# Version_1.net
KiCad netlist of a schematic drawn in EAGLE
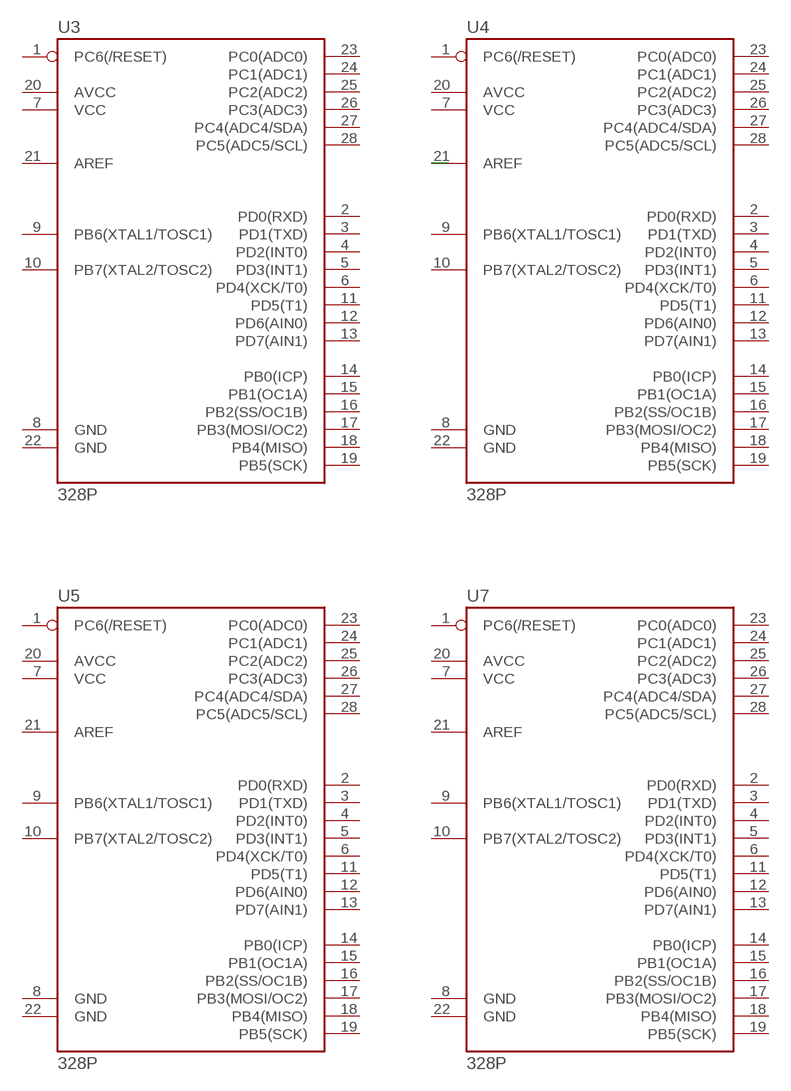
[diagram p0: schematic, sheet 1, part 1 of 2]
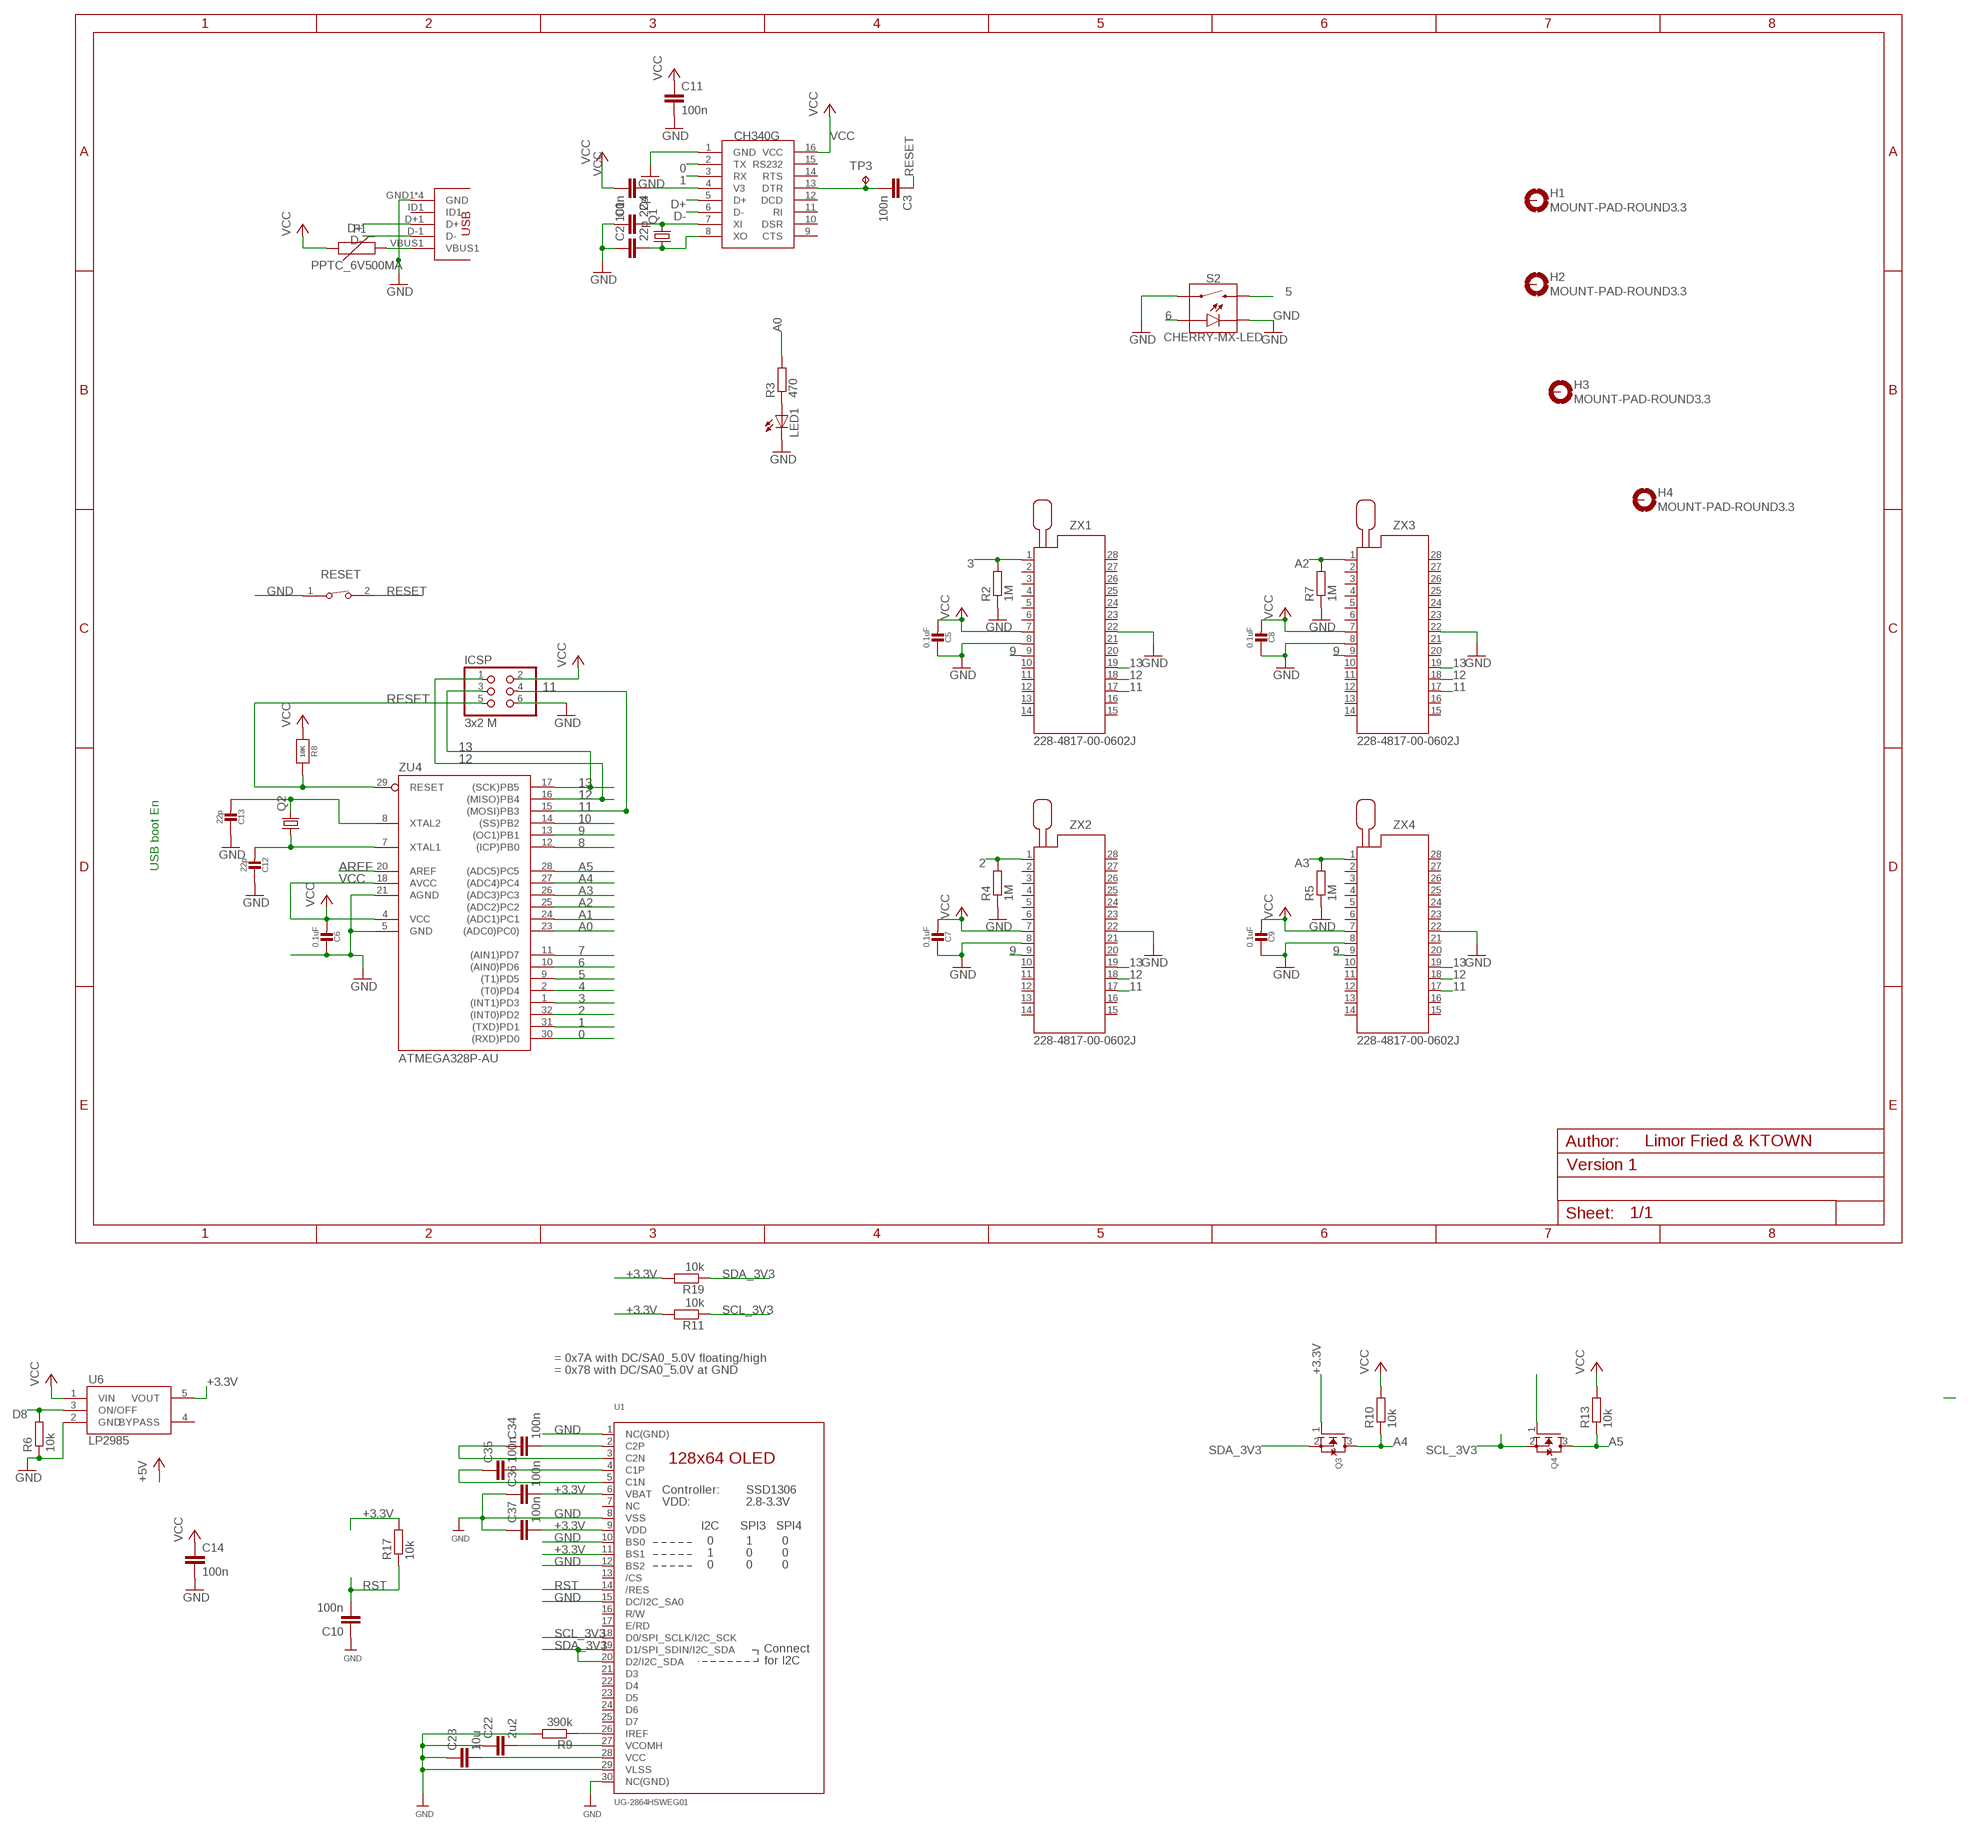
[diagram p1: schematic, sheet 1, part 2 of 2]

(export (version "E")
  (design (tool "Eeschema 10.0.6"))
  (components
    (comp (ref "C1")
      (value "22p")
      (footprint "eagle-import:C0805")
      (libsource (lib "eagle-import") (part "resistor_C-EUC0805"))
    )
    (comp (ref "C2")
      (value "22p")
      (footprint "eagle-import:C0805")
      (libsource (lib "eagle-import") (part "resistor_C-EUC0805"))
    )
    (comp (ref "C3")
      (value "100n")
      (footprint "eagle-import:C0805")
      (libsource (lib "eagle-import") (part "resistor_C-EUC0805"))
    )
    (comp (ref "C4")
      (value "100n")
      (footprint "eagle-import:C0805")
      (libsource (lib "eagle-import") (part "resistor_C-EUC0805"))
    )
    (comp (ref "C5")
      (value "0.1uF")
      (footprint "eagle-import:0805-NO")
      (libsource (lib "eagle-import") (part "CAP_CERAMIC0805-NOOUTLINE"))
    )
    (comp (ref "C6")
      (value "0.1uF")
      (footprint "eagle-import:0805-NO")
      (libsource (lib "eagle-import") (part "CAP_CERAMIC0805-NOOUTLINE"))
    )
    (comp (ref "C7")
      (value "0.1uF")
      (footprint "eagle-import:0805-NO")
      (libsource (lib "eagle-import") (part "CAP_CERAMIC0805-NOOUTLINE"))
    )
    (comp (ref "C8")
      (value "0.1uF")
      (footprint "eagle-import:0805-NO")
      (libsource (lib "eagle-import") (part "CAP_CERAMIC0805-NOOUTLINE"))
    )
    (comp (ref "C9")
      (value "0.1uF")
      (footprint "eagle-import:0805-NO")
      (libsource (lib "eagle-import") (part "CAP_CERAMIC0805-NOOUTLINE"))
    )
    (comp (ref "C10")
      (value "100n")
      (footprint "eagle-import:C0805")
      (libsource (lib "eagle-import") (part "C-EUC0805"))
    )
    (comp (ref "C11")
      (value "100n")
      (footprint "eagle-import:C0805")
      (libsource (lib "eagle-import") (part "resistor_C-EUC0805"))
    )
    (comp (ref "C12")
      (value "22p")
      (footprint "eagle-import:0805_10MGAP")
      (libsource (lib "eagle-import") (part "CAP_CERAMIC0805_10MGAP"))
    )
    (comp (ref "C13")
      (value "22p")
      (footprint "eagle-import:0805_10MGAP")
      (libsource (lib "eagle-import") (part "CAP_CERAMIC0805_10MGAP"))
    )
    (comp (ref "C14")
      (value "100n")
      (footprint "eagle-import:C0805")
      (libsource (lib "eagle-import") (part "resistor_C-EUC0805"))
    )
    (comp (ref "C22")
      (value "2u2")
      (footprint "eagle-import:C0805")
      (libsource (lib "eagle-import") (part "C-EUC0805"))
    )
    (comp (ref "C23")
      (value "10u")
      (footprint "eagle-import:C0805")
      (libsource (lib "eagle-import") (part "C-EUC0805"))
    )
    (comp (ref "C34")
      (value "100n")
      (footprint "eagle-import:C0805")
      (libsource (lib "eagle-import") (part "C-EUC0805"))
    )
    (comp (ref "C35")
      (value "100n")
      (footprint "eagle-import:C0805")
      (libsource (lib "eagle-import") (part "C-EUC0805"))
    )
    (comp (ref "C36")
      (value "100n")
      (footprint "eagle-import:C0805")
      (libsource (lib "eagle-import") (part "C-EUC0805"))
    )
    (comp (ref "C37")
      (value "100n")
      (footprint "eagle-import:C0805")
      (libsource (lib "eagle-import") (part "C-EUC0805"))
    )
    (comp (ref "F1")
      (value "PPTC_6V500MA")
      (footprint "eagle-import:0805")
      (libsource (lib "eagle-import") (part "PPTC_6V500MA"))
    )
    (comp (ref "H1")
      (value "MOUNT-PAD-ROUND3.3")
      (footprint "eagle-import:3,3-PAD")
      (libsource (lib "eagle-import") (part "MOUNT-PAD-ROUND3.3"))
    )
    (comp (ref "H2")
      (value "MOUNT-PAD-ROUND3.3")
      (footprint "eagle-import:3,3-PAD")
      (libsource (lib "eagle-import") (part "MOUNT-PAD-ROUND3.3"))
    )
    (comp (ref "H3")
      (value "MOUNT-PAD-ROUND3.3")
      (footprint "eagle-import:3,3-PAD")
      (libsource (lib "eagle-import") (part "MOUNT-PAD-ROUND3.3"))
    )
    (comp (ref "H4")
      (value "MOUNT-PAD-ROUND3.3")
      (footprint "eagle-import:3,3-PAD")
      (libsource (lib "eagle-import") (part "MOUNT-PAD-ROUND3.3"))
    )
    (comp (ref "ICSP")
      (value "3x2 M")
      (footprint "eagle-import:2X03_ROUND_70MIL")
      (libsource (lib "eagle-import") (part "HEADER-2X3"))
    )
    (comp (ref "J1")
      (value "USB-AB")
      (footprint "eagle-import:USB-AB-MICRO-SMD_V02_BOSS")
      (libsource (lib "eagle-import") (part "USB-AB"))
    )
    (comp (ref "LED1")
      (value "LEDCHIPLED_0805")
      (footprint "eagle-import:CHIPLED_0805")
      (libsource (lib "eagle-import") (part "LEDCHIPLED_0805"))
    )
    (comp (ref "Q1")
      (value "CRYSTALHC49S")
      (footprint "eagle-import:HC49_S")
      (libsource (lib "eagle-import") (part "CRYSTALHC49S"))
    )
    (comp (ref "Q2")
      (value "CRYSTALHC49S")
      (footprint "eagle-import:HC49_S")
      (libsource (lib "eagle-import") (part "CRYSTALHC49S"))
    )
    (comp (ref "Q3")
      (value "MOSFET-NREFLOW")
      (footprint "eagle-import:SOT23")
      (libsource (lib "eagle-import") (part "MOSFET-NREFLOW"))
    )
    (comp (ref "Q4")
      (value "MOSFET-NREFLOW")
      (footprint "eagle-import:SOT23")
      (libsource (lib "eagle-import") (part "MOSFET-NREFLOW"))
    )
    (comp (ref "R2")
      (value "1M")
      (footprint "eagle-import:R0805")
      (libsource (lib "eagle-import") (part "resistor_R-EU_R0805"))
    )
    (comp (ref "R3")
      (value "470")
      (footprint "eagle-import:R0805")
      (libsource (lib "eagle-import") (part "resistor_R-EU_R0805"))
    )
    (comp (ref "R4")
      (value "1M")
      (footprint "eagle-import:R0805")
      (libsource (lib "eagle-import") (part "resistor_R-EU_R0805"))
    )
    (comp (ref "R5")
      (value "1M")
      (footprint "eagle-import:R0805")
      (libsource (lib "eagle-import") (part "resistor_R-EU_R0805"))
    )
    (comp (ref "R6")
      (value "10k")
      (footprint "eagle-import:R0805")
      (libsource (lib "eagle-import") (part "R-EU_R0805"))
    )
    (comp (ref "R7")
      (value "1M")
      (footprint "eagle-import:R0805")
      (libsource (lib "eagle-import") (part "resistor_R-EU_R0805"))
    )
    (comp (ref "R8")
      (value "10K")
      (footprint "eagle-import:_0805MP")
      (libsource (lib "eagle-import") (part "RESISTOR_0805MP"))
    )
    (comp (ref "R9")
      (value "390k")
      (footprint "eagle-import:R0805")
      (libsource (lib "eagle-import") (part "R-EU_R0805"))
    )
    (comp (ref "R10")
      (value "10k")
      (footprint "eagle-import:R0805")
      (libsource (lib "eagle-import") (part "R-EU_R0805"))
    )
    (comp (ref "R11")
      (value "10k")
      (footprint "eagle-import:R0805")
      (libsource (lib "eagle-import") (part "R-EU_R0805"))
    )
    (comp (ref "R13")
      (value "10k")
      (footprint "eagle-import:R0805")
      (libsource (lib "eagle-import") (part "R-EU_R0805"))
    )
    (comp (ref "R17")
      (value "10k")
      (footprint "eagle-import:R0805")
      (libsource (lib "eagle-import") (part "R-EU_R0805"))
    )
    (comp (ref "R19")
      (value "10k")
      (footprint "eagle-import:R0805")
      (libsource (lib "eagle-import") (part "R-EU_R0805"))
    )
    (comp (ref "RESET")
      (value "434111043826")
      (footprint "eagle-import:434111043826")
      (libsource (lib "eagle-import") (part "434111043826"))
    )
    (comp (ref "S2")
      (value "CHERRY-MX-LED")
      (footprint "eagle-import:CHERRY-MX-LED")
      (libsource (lib "eagle-import") (part "CHERRY-MX-LED"))
    )
    (comp (ref "TP3")
      (value "TPTP18R")
      (footprint "eagle-import:TP18R")
      (libsource (lib "eagle-import") (part "TPTP18R"))
    )
    (comp (ref "U1")
      (value "UG-2864HSWEG01")
      (footprint "eagle-import:UG-2864HSWEG01_0.96IN_WRAPAROUND")
      (libsource (lib "eagle-import") (part "DISP_OLED_UG-2864HSWEG010.96{dblquote}"))
    )
    (comp (ref "U2")
      (value "CH340G")
      (footprint "eagle-import:SOIC16")
      (libsource (lib "eagle-import") (part "CH340G"))
    )
    (comp (ref "U3")
      (value "328P")
      (footprint "eagle-import:DIP28")
      (libsource (lib "eagle-import") (part "ATMEGA328P_PDIP"))
    )
    (comp (ref "U4")
      (value "328P")
      (footprint "eagle-import:DIP28")
      (libsource (lib "eagle-import") (part "ATMEGA328P_PDIP"))
    )
    (comp (ref "U5")
      (value "328P")
      (footprint "eagle-import:DIP28")
      (libsource (lib "eagle-import") (part "ATMEGA328P_PDIP"))
    )
    (comp (ref "U6")
      (value "LP2985AIM5-3.3")
      (footprint "eagle-import:SOT25")
      (libsource (lib "eagle-import") (part "LP2985AIM5-3.3"))
    )
    (comp (ref "U7")
      (value "328P")
      (footprint "eagle-import:DIP28")
      (libsource (lib "eagle-import") (part "ATMEGA328P_PDIP"))
    )
    (comp (ref "ZU4")
      (value "ATMEGA328P-AU")
      (footprint "eagle-import:TQFP32-08")
      (libsource (lib "eagle-import") (part "ATMEGA328P-AU"))
    )
    (comp (ref "ZX1")
      (value "228-4817-00-0602J")
      (footprint "eagle-import:228-4817-00-0602J")
      (fields (field (name "MF") "3M"))
      (libsource (lib "eagle-import") (part "228-?00-0602J4817-"))
    )
    (comp (ref "ZX2")
      (value "228-4817-00-0602J")
      (footprint "eagle-import:228-4817-00-0602J")
      (fields (field (name "MF") "3M"))
      (libsource (lib "eagle-import") (part "228-?00-0602J4817-"))
    )
    (comp (ref "ZX3")
      (value "228-4817-00-0602J")
      (footprint "eagle-import:228-4817-00-0602J")
      (fields (field (name "MF") "3M"))
      (libsource (lib "eagle-import") (part "228-?00-0602J4817-"))
    )
    (comp (ref "ZX4")
      (value "228-4817-00-0602J")
      (footprint "eagle-import:228-4817-00-0602J")
      (fields (field (name "MF") "3M"))
      (libsource (lib "eagle-import") (part "228-?00-0602J4817-"))
    )
  )
  (nets
    (net (code "2") (name "/+3.3V") (class "Default")
      (node (ref "C36") (pin "2") (pinfunction "2_2") (pintype "passive"))
      (node (ref "C37") (pin "2") (pinfunction "2_2") (pintype "passive"))
      (node (ref "Q3") (pin "1") (pinfunction "G_1") (pintype "bidirectional"))
      (node (ref "Q4") (pin "1") (pinfunction "G_1") (pintype "bidirectional"))
      (node (ref "R11") (pin "2") (pinfunction "2_2") (pintype "passive"))
      (node (ref "R17") (pin "2") (pinfunction "2_2") (pintype "passive"))
      (node (ref "R19") (pin "2") (pinfunction "2_2") (pintype "passive"))
      (node (ref "U1") (pin "11") (pinfunction "BS1_11") (pintype "input"))
      (node (ref "U1") (pin "6") (pinfunction "VBAT_6") (pintype "input"))
      (node (ref "U1") (pin "9") (pinfunction "VDD_9") (pintype "power_in"))
      (node (ref "U6") (pin "5") (pinfunction "VOUT_5") (pintype "power_in"))
    )
    (net (code "3") (name "/0") (class "Default")
      (node (ref "U2") (pin "2") (pinfunction "TX_2") (pintype "bidirectional"))
      (node (ref "ZU4") (pin "30") (pinfunction "(RXD)PD0_30") (pintype "bidirectional"))
    )
    (net (code "4") (name "/1") (class "Default")
      (node (ref "U2") (pin "3") (pinfunction "RX_3") (pintype "bidirectional"))
      (node (ref "ZU4") (pin "31") (pinfunction "(TXD)PD1_31") (pintype "bidirectional"))
    )
    (net (code "5") (name "/2") (class "Default")
      (node (ref "R4") (pin "2") (pinfunction "2_2") (pintype "passive"))
      (node (ref "ZU4") (pin "32") (pinfunction "(INT0)PD2_32") (pintype "bidirectional"))
      (node (ref "ZX2") (pin "1") (pinfunction "1_1") (pintype "passive"))
    )
    (net (code "6") (name "/3") (class "Default")
      (node (ref "R2") (pin "2") (pinfunction "2_2") (pintype "passive"))
      (node (ref "ZU4") (pin "1") (pinfunction "(INT1)PD3_1") (pintype "bidirectional"))
      (node (ref "ZX1") (pin "1") (pinfunction "1_1") (pintype "passive"))
    )
    (net (code "7") (name "/4") (class "Default")
      (node (ref "ZU4") (pin "2") (pinfunction "(T0)PD4_2") (pintype "bidirectional"))
    )
    (net (code "8") (name "/5") (class "Default")
      (node (ref "S2") (pin "S2") (pinfunction "S2_S2") (pintype "passive"))
      (node (ref "ZU4") (pin "9") (pinfunction "(T1)PD5_9") (pintype "bidirectional"))
    )
    (net (code "9") (name "/6") (class "Default")
      (node (ref "S2") (pin "A") (pinfunction "A_A") (pintype "passive"))
      (node (ref "ZU4") (pin "10") (pinfunction "(AIN0)PD6_10") (pintype "bidirectional"))
    )
    (net (code "10") (name "/7") (class "Default")
      (node (ref "ZU4") (pin "11") (pinfunction "(AIN1)PD7_11") (pintype "bidirectional"))
    )
    (net (code "11") (name "/8") (class "Default")
      (node (ref "ZU4") (pin "12") (pinfunction "(ICP)PB0_12") (pintype "bidirectional"))
    )
    (net (code "12") (name "/9") (class "Default")
      (node (ref "ZU4") (pin "13") (pinfunction "(OC1)PB1_13") (pintype "bidirectional"))
      (node (ref "ZX1") (pin "9") (pinfunction "9_9") (pintype "passive"))
      (node (ref "ZX2") (pin "9") (pinfunction "9_9") (pintype "passive"))
      (node (ref "ZX3") (pin "9") (pinfunction "9_9") (pintype "passive"))
      (node (ref "ZX4") (pin "9") (pinfunction "9_9") (pintype "passive"))
    )
    (net (code "13") (name "/10") (class "Default")
      (node (ref "ZU4") (pin "14") (pinfunction "(SS)PB2_14") (pintype "bidirectional"))
    )
    (net (code "14") (name "/11") (class "Default")
      (node (ref "ICSP") (pin "4") (pinfunction "4_4") (pintype "passive"))
      (node (ref "ZU4") (pin "15") (pinfunction "(MOSI)PB3_15") (pintype "bidirectional"))
      (node (ref "ZX1") (pin "17") (pinfunction "17_17") (pintype "passive"))
      (node (ref "ZX2") (pin "17") (pinfunction "17_17") (pintype "passive"))
      (node (ref "ZX3") (pin "17") (pinfunction "17_17") (pintype "passive"))
      (node (ref "ZX4") (pin "17") (pinfunction "17_17") (pintype "passive"))
    )
    (net (code "15") (name "/12") (class "Default")
      (node (ref "ICSP") (pin "1") (pinfunction "1_1") (pintype "passive"))
      (node (ref "ZU4") (pin "16") (pinfunction "(MISO)PB4_16") (pintype "bidirectional"))
      (node (ref "ZX1") (pin "18") (pinfunction "18_18") (pintype "passive"))
      (node (ref "ZX2") (pin "18") (pinfunction "18_18") (pintype "passive"))
      (node (ref "ZX3") (pin "18") (pinfunction "18_18") (pintype "passive"))
      (node (ref "ZX4") (pin "18") (pinfunction "18_18") (pintype "passive"))
    )
    (net (code "16") (name "/13") (class "Default")
      (node (ref "ICSP") (pin "3") (pinfunction "3_3") (pintype "passive"))
      (node (ref "ZU4") (pin "17") (pinfunction "(SCK)PB5_17") (pintype "bidirectional"))
      (node (ref "ZX1") (pin "19") (pinfunction "19_19") (pintype "passive"))
      (node (ref "ZX2") (pin "19") (pinfunction "19_19") (pintype "passive"))
      (node (ref "ZX3") (pin "19") (pinfunction "19_19") (pintype "passive"))
      (node (ref "ZX4") (pin "19") (pinfunction "19_19") (pintype "passive"))
    )
    (net (code "17") (name "/A0") (class "Default")
      (node (ref "R3") (pin "2") (pinfunction "2_2") (pintype "passive"))
      (node (ref "ZU4") (pin "23") (pinfunction "(ADC0)PC0)_23") (pintype "bidirectional"))
    )
    (net (code "18") (name "/A1") (class "Default")
      (node (ref "ZU4") (pin "24") (pinfunction "(ADC1)PC1_24") (pintype "bidirectional"))
    )
    (net (code "19") (name "/A2") (class "Default")
      (node (ref "R7") (pin "2") (pinfunction "2_2") (pintype "passive"))
      (node (ref "ZU4") (pin "25") (pinfunction "(ADC2)PC2_25") (pintype "bidirectional"))
      (node (ref "ZX3") (pin "1") (pinfunction "1_1") (pintype "passive"))
    )
    (net (code "20") (name "/A3") (class "Default")
      (node (ref "R5") (pin "2") (pinfunction "2_2") (pintype "passive"))
      (node (ref "ZU4") (pin "26") (pinfunction "(ADC3)PC3_26") (pintype "bidirectional"))
      (node (ref "ZX4") (pin "1") (pinfunction "1_1") (pintype "passive"))
    )
    (net (code "21") (name "/A4") (class "Default")
      (node (ref "Q3") (pin "3") (pinfunction "D_3") (pintype "bidirectional"))
      (node (ref "R10") (pin "1") (pinfunction "1_1") (pintype "passive"))
      (node (ref "ZU4") (pin "27") (pinfunction "(ADC4)PC4_27") (pintype "bidirectional"))
    )
    (net (code "22") (name "/A5") (class "Default")
      (node (ref "Q4") (pin "3") (pinfunction "D_3") (pintype "bidirectional"))
      (node (ref "R13") (pin "1") (pinfunction "1_1") (pintype "passive"))
      (node (ref "ZU4") (pin "28") (pinfunction "(ADC5)PC5_28") (pintype "bidirectional"))
    )
    (net (code "23") (name "/AREF") (class "Default")
      (node (ref "ZU4") (pin "20") (pinfunction "AREF_20") (pintype "passive"))
    )
    (net (code "24") (name "/BYPASS") (class "Default")
      (node (ref "U6") (pin "4") (pinfunction "BYPASS_4") (pintype "power_in"))
    )
    (net (code "25") (name "/D+") (class "Default")
      (node (ref "J1") (pin "D+1") (pinfunction "D+_D+1") (pintype "bidirectional"))
      (node (ref "U2") (pin "5") (pinfunction "D+_5") (pintype "bidirectional"))
    )
    (net (code "26") (name "/D-") (class "Default")
      (node (ref "J1") (pin "D-1") (pinfunction "D-_D-1") (pintype "bidirectional"))
      (node (ref "U2") (pin "6") (pinfunction "D-_6") (pintype "bidirectional"))
    )
    (net (code "27") (name "/D8") (class "Default")
      (node (ref "R6") (pin "2") (pinfunction "2_2") (pintype "passive"))
      (node (ref "U6") (pin "3") (pinfunction "ON/OFF_3") (pintype "input"))
    )
    (net (code "28") (name "/RESET") (class "Default")
      (node (ref "C3") (pin "1") (pinfunction "1_1") (pintype "passive"))
      (node (ref "ICSP") (pin "5") (pinfunction "5_5") (pintype "passive"))
      (node (ref "R8") (pin "1") (pinfunction "1_1") (pintype "passive"))
      (node (ref "RESET") (pin "2") (pinfunction "2_2") (pintype "passive"))
      (node (ref "ZU4") (pin "29") (pinfunction "RESET_29") (pintype "input"))
    )
    (net (code "29") (name "/RST") (class "Default")
      (node (ref "C10") (pin "2") (pinfunction "2_2") (pintype "passive"))
      (node (ref "R17") (pin "1") (pinfunction "1_1") (pintype "passive"))
      (node (ref "U1") (pin "14") (pinfunction "/RES_14") (pintype "input"))
    )
    (net (code "30") (name "/SCL_3V3") (class "Default")
      (node (ref "Q4") (pin "2") (pinfunction "S_2") (pintype "bidirectional"))
      (node (ref "R11") (pin "1") (pinfunction "1_1") (pintype "passive"))
      (node (ref "U1") (pin "18") (pinfunction "D0/SPI_SCLK/I2C_SCK_18") (pintype "bidirectional"))
    )
    (net (code "31") (name "/SDA_3V3") (class "Default")
      (node (ref "Q3") (pin "2") (pinfunction "S_2") (pintype "bidirectional"))
      (node (ref "R19") (pin "1") (pinfunction "1_1") (pintype "passive"))
      (node (ref "U1") (pin "19") (pinfunction "D1/SPI_SDIN/I2C_SDA_19") (pintype "bidirectional"))
      (node (ref "U1") (pin "20") (pinfunction "D2/I2C_SDA_20") (pintype "bidirectional"))
    )
    (net (code "32") (name "GND") (class "Default")
      (node (ref "C1") (pin "1") (pinfunction "1_1") (pintype "passive"))
      (node (ref "C10") (pin "1") (pinfunction "1_1") (pintype "passive"))
      (node (ref "C11") (pin "2") (pinfunction "2_2") (pintype "passive"))
      (node (ref "C12") (pin "1") (pinfunction "1_1") (pintype "passive"))
      (node (ref "C13") (pin "1") (pinfunction "1_1") (pintype "passive"))
      (node (ref "C14") (pin "2") (pinfunction "2_2") (pintype "passive"))
      (node (ref "C2") (pin "1") (pinfunction "1_1") (pintype "passive"))
      (node (ref "C22") (pin "1") (pinfunction "1_1") (pintype "passive"))
      (node (ref "C23") (pin "1") (pinfunction "1_1") (pintype "passive"))
      (node (ref "C36") (pin "1") (pinfunction "1_1") (pintype "passive"))
      (node (ref "C37") (pin "1") (pinfunction "1_1") (pintype "passive"))
      (node (ref "C5") (pin "1") (pinfunction "1_1") (pintype "passive"))
      (node (ref "C6") (pin "1") (pinfunction "1_1") (pintype "passive"))
      (node (ref "C7") (pin "1") (pinfunction "1_1") (pintype "passive"))
      (node (ref "C8") (pin "1") (pinfunction "1_1") (pintype "passive"))
      (node (ref "C9") (pin "1") (pinfunction "1_1") (pintype "passive"))
      (node (ref "ICSP") (pin "6") (pinfunction "6_6") (pintype "passive"))
      (node (ref "J1") (pin "GND1") (pinfunction "GND_GND1") (pintype "bidirectional"))
      (node (ref "J1") (pin "P$1") (pinfunction "GND_P$1") (pintype "bidirectional"))
      (node (ref "J1") (pin "P$2") (pinfunction "GND_P$2") (pintype "bidirectional"))
      (node (ref "J1") (pin "P$3") (pinfunction "GND_P$3") (pintype "bidirectional"))
      (node (ref "LED1") (pin "C") (pinfunction "C_C") (pintype "passive"))
      (node (ref "R2") (pin "1") (pinfunction "1_1") (pintype "passive"))
      (node (ref "R4") (pin "1") (pinfunction "1_1") (pintype "passive"))
      (node (ref "R5") (pin "1") (pinfunction "1_1") (pintype "passive"))
      (node (ref "R6") (pin "1") (pinfunction "1_1") (pintype "passive"))
      (node (ref "R7") (pin "1") (pinfunction "1_1") (pintype "passive"))
      (node (ref "R9") (pin "2") (pinfunction "2_2") (pintype "passive"))
      (node (ref "RESET") (pin "1") (pinfunction "1_1") (pintype "passive"))
      (node (ref "S2") (pin "K") (pinfunction "C_K") (pintype "passive"))
      (node (ref "S2") (pin "S1") (pinfunction "S1_S1") (pintype "passive"))
      (node (ref "U1") (pin "1") (pinfunction "NC(GND)_1") (pintype "input"))
      (node (ref "U1") (pin "10") (pinfunction "BS0_10") (pintype "input"))
      (node (ref "U1") (pin "12") (pinfunction "BS2_12") (pintype "input"))
      (node (ref "U1") (pin "15") (pinfunction "DC/I2C_SA0_15") (pintype "input"))
      (node (ref "U1") (pin "29") (pinfunction "VLSS_29") (pintype "power_in"))
      (node (ref "U1") (pin "30") (pinfunction "NC(GND)_30") (pintype "input"))
      (node (ref "U1") (pin "8") (pinfunction "VSS_8") (pintype "power_in"))
      (node (ref "U2") (pin "1") (pinfunction "GND_1") (pintype "bidirectional"))
      (node (ref "U6") (pin "2") (pinfunction "GND_2") (pintype "power_in"))
      (node (ref "ZU4") (pin "21") (pinfunction "AGND_21") (pintype "power_in"))
      (node (ref "ZU4") (pin "5") (pinfunction "GND_5") (pintype "power_in"))
      (node (ref "ZX1") (pin "22") (pinfunction "22_22") (pintype "passive"))
      (node (ref "ZX1") (pin "8") (pinfunction "8_8") (pintype "passive"))
      (node (ref "ZX2") (pin "22") (pinfunction "22_22") (pintype "passive"))
      (node (ref "ZX2") (pin "8") (pinfunction "8_8") (pintype "passive"))
      (node (ref "ZX3") (pin "22") (pinfunction "22_22") (pintype "passive"))
      (node (ref "ZX3") (pin "8") (pinfunction "8_8") (pintype "passive"))
      (node (ref "ZX4") (pin "22") (pinfunction "22_22") (pintype "passive"))
      (node (ref "ZX4") (pin "8") (pinfunction "8_8") (pintype "passive"))
    )
    (net (code "33") (name "Net-(F1-Pad2)") (class "Default")
      (node (ref "F1") (pin "2") (pinfunction "2_2") (pintype "bidirectional"))
      (node (ref "J1") (pin "VBUS1") (pinfunction "VBUS1_VBUS1") (pintype "bidirectional"))
    )
    (net (code "34") (name "Net-(LED1-PadA)") (class "Default")
      (node (ref "LED1") (pin "A") (pinfunction "A_A") (pintype "passive"))
      (node (ref "R3") (pin "1") (pinfunction "1_1") (pintype "passive"))
    )
    (net (code "35") (name "Net-(U1-C1N)") (class "Default")
      (node (ref "C35") (pin "1") (pinfunction "1_1") (pintype "passive"))
      (node (ref "U1") (pin "5") (pinfunction "C1N_5") (pintype "input"))
    )
    (net (code "36") (name "Net-(U1-C1P)") (class "Default")
      (node (ref "C35") (pin "2") (pinfunction "2_2") (pintype "passive"))
      (node (ref "U1") (pin "4") (pinfunction "C1P_4") (pintype "input"))
    )
    (net (code "37") (name "Net-(U1-C2N)") (class "Default")
      (node (ref "C34") (pin "1") (pinfunction "1_1") (pintype "passive"))
      (node (ref "U1") (pin "3") (pinfunction "C2N_3") (pintype "input"))
    )
    (net (code "38") (name "Net-(U1-C2P)") (class "Default")
      (node (ref "C34") (pin "2") (pinfunction "2_2") (pintype "passive"))
      (node (ref "U1") (pin "2") (pinfunction "C2P_2") (pintype "input"))
    )
    (net (code "39") (name "Net-(U1-IREF)") (class "Default")
      (node (ref "R9") (pin "1") (pinfunction "1_1") (pintype "passive"))
      (node (ref "U1") (pin "26") (pinfunction "IREF_26") (pintype "input"))
    )
    (net (code "40") (name "Net-(U1-VCC)") (class "Default")
      (node (ref "C23") (pin "2") (pinfunction "2_2") (pintype "passive"))
      (node (ref "U1") (pin "28") (pinfunction "VCC_28") (pintype "power_in"))
    )
    (net (code "41") (name "Net-(U1-VCOMH)") (class "Default")
      (node (ref "C22") (pin "2") (pinfunction "2_2") (pintype "passive"))
      (node (ref "U1") (pin "27") (pinfunction "VCOMH_27") (pintype "output"))
    )
    (net (code "42") (name "Net-(U2-DTR)") (class "Default")
      (node (ref "C3") (pin "2") (pinfunction "2_2") (pintype "passive"))
      (node (ref "TP3") (pin "TP") (pinfunction "TP_TP") (pintype "input"))
      (node (ref "U2") (pin "13") (pinfunction "DTR_13") (pintype "bidirectional"))
    )
    (net (code "43") (name "Net-(U2-V3)") (class "Default")
      (node (ref "C4") (pin "1") (pinfunction "1_1") (pintype "passive"))
      (node (ref "U2") (pin "4") (pinfunction "V3_4") (pintype "bidirectional"))
    )
    (net (code "44") (name "Net-(U2-XI)") (class "Default")
      (node (ref "C1") (pin "2") (pinfunction "2_2") (pintype "passive"))
      (node (ref "Q1") (pin "2") (pinfunction "2_2") (pintype "passive"))
      (node (ref "U2") (pin "7") (pinfunction "XI_7") (pintype "bidirectional"))
    )
    (net (code "45") (name "Net-(U2-XO)") (class "Default")
      (node (ref "C2") (pin "2") (pinfunction "2_2") (pintype "passive"))
      (node (ref "Q1") (pin "1") (pinfunction "1_1") (pintype "passive"))
      (node (ref "U2") (pin "8") (pinfunction "XO_8") (pintype "bidirectional"))
    )
    (net (code "46") (name "Net-(ZU4-XTAL1)") (class "Default")
      (node (ref "C12") (pin "2") (pinfunction "2_2") (pintype "passive"))
      (node (ref "Q2") (pin "1") (pinfunction "1_1") (pintype "passive"))
      (node (ref "ZU4") (pin "7") (pinfunction "XTAL1_7") (pintype "bidirectional"))
    )
    (net (code "47") (name "Net-(ZU4-XTAL2)") (class "Default")
      (node (ref "C13") (pin "2") (pinfunction "2_2") (pintype "passive"))
      (node (ref "Q2") (pin "2") (pinfunction "2_2") (pintype "passive"))
      (node (ref "ZU4") (pin "8") (pinfunction "XTAL2_8") (pintype "bidirectional"))
    )
    (net (code "48") (name "VCC") (class "Default")
      (node (ref "C11") (pin "1") (pinfunction "1_1") (pintype "passive"))
      (node (ref "C14") (pin "1") (pinfunction "1_1") (pintype "passive"))
      (node (ref "C4") (pin "2") (pinfunction "2_2") (pintype "passive"))
      (node (ref "C5") (pin "2") (pinfunction "2_2") (pintype "passive"))
      (node (ref "C6") (pin "2") (pinfunction "2_2") (pintype "passive"))
      (node (ref "C7") (pin "2") (pinfunction "2_2") (pintype "passive"))
      (node (ref "C8") (pin "2") (pinfunction "2_2") (pintype "passive"))
      (node (ref "C9") (pin "2") (pinfunction "2_2") (pintype "passive"))
      (node (ref "F1") (pin "1") (pinfunction "1_1") (pintype "bidirectional"))
      (node (ref "ICSP") (pin "2") (pinfunction "2_2") (pintype "passive"))
      (node (ref "R10") (pin "2") (pinfunction "2_2") (pintype "passive"))
      (node (ref "R13") (pin "2") (pinfunction "2_2") (pintype "passive"))
      (node (ref "R8") (pin "2") (pinfunction "2_2") (pintype "passive"))
      (node (ref "U2") (pin "16") (pinfunction "VCC_16") (pintype "bidirectional"))
      (node (ref "U6") (pin "1") (pinfunction "VIN_1") (pintype "power_in"))
      (node (ref "ZU4") (pin "18") (pinfunction "AVCC_18") (pintype "power_in"))
      (node (ref "ZU4") (pin "4") (pinfunction "VCC_4") (pintype "power_in"))
      (node (ref "ZX1") (pin "7") (pinfunction "7_7") (pintype "passive"))
      (node (ref "ZX2") (pin "7") (pinfunction "7_7") (pintype "passive"))
      (node (ref "ZX3") (pin "7") (pinfunction "7_7") (pintype "passive"))
      (node (ref "ZX4") (pin "7") (pinfunction "7_7") (pintype "passive"))
    )
    (net (code "49") (name "unconnected-(H1-MOUNT-PadB3,3)") (class "Default")
      (node (ref "H1") (pin "B3,3") (pinfunction "MOUNT_B3,3") (pintype "passive"))
    )
    (net (code "50") (name "unconnected-(H2-MOUNT-PadB3,3)") (class "Default")
      (node (ref "H2") (pin "B3,3") (pinfunction "MOUNT_B3,3") (pintype "passive"))
    )
    (net (code "51") (name "unconnected-(H3-MOUNT-PadB3,3)") (class "Default")
      (node (ref "H3") (pin "B3,3") (pinfunction "MOUNT_B3,3") (pintype "passive"))
    )
    (net (code "52") (name "unconnected-(H4-MOUNT-PadB3,3)") (class "Default")
      (node (ref "H4") (pin "B3,3") (pinfunction "MOUNT_B3,3") (pintype "passive"))
    )
    (net (code "53") (name "unconnected-(J1-PadID1)") (class "Default")
      (node (ref "J1") (pin "ID1") (pinfunction "ID1_ID1") (pintype "bidirectional"))
    )
    (net (code "54") (name "unconnected-(U1-D3-Pad21)") (class "Default")
      (node (ref "U1") (pin "21") (pinfunction "D3_21") (pintype "bidirectional"))
    )
    (net (code "55") (name "unconnected-(U1-D4-Pad22)") (class "Default")
      (node (ref "U1") (pin "22") (pinfunction "D4_22") (pintype "bidirectional"))
    )
    (net (code "56") (name "unconnected-(U1-D5-Pad23)") (class "Default")
      (node (ref "U1") (pin "23") (pinfunction "D5_23") (pintype "bidirectional"))
    )
    (net (code "57") (name "unconnected-(U1-D6-Pad24)") (class "Default")
      (node (ref "U1") (pin "24") (pinfunction "D6_24") (pintype "bidirectional"))
    )
    (net (code "58") (name "unconnected-(U1-D7-Pad25)") (class "Default")
      (node (ref "U1") (pin "25") (pinfunction "D7_25") (pintype "bidirectional"))
    )
    (net (code "59") (name "unconnected-(U1-E{slash}RD-Pad17)") (class "Default")
      (node (ref "U1") (pin "17") (pinfunction "E/RD_17") (pintype "input"))
    )
    (net (code "60") (name "unconnected-(U1-NC-Pad7)") (class "Default")
      (node (ref "U1") (pin "7") (pinfunction "NC_7") (pintype "no_connect"))
    )
    (net (code "61") (name "unconnected-(U1-R{slash}W-Pad16)") (class "Default")
      (node (ref "U1") (pin "16") (pinfunction "R/W_16") (pintype "input"))
    )
    (net (code "62") (name "unconnected-(U1-{slash}CS-Pad13)") (class "Default")
      (node (ref "U1") (pin "13") (pinfunction "/CS_13") (pintype "input"))
    )
    (net (code "63") (name "unconnected-(U2-CTS-Pad9)") (class "Default")
      (node (ref "U2") (pin "9") (pinfunction "CTS_9") (pintype "bidirectional"))
    )
    (net (code "64") (name "unconnected-(U2-DCD-Pad12)") (class "Default")
      (node (ref "U2") (pin "12") (pinfunction "DCD_12") (pintype "bidirectional"))
    )
    (net (code "65") (name "unconnected-(U2-DSR-Pad10)") (class "Default")
      (node (ref "U2") (pin "10") (pinfunction "DSR_10") (pintype "bidirectional"))
    )
    (net (code "66") (name "unconnected-(U2-RI-Pad11)") (class "Default")
      (node (ref "U2") (pin "11") (pinfunction "RI_11") (pintype "bidirectional"))
    )
    (net (code "67") (name "unconnected-(U2-RS232-Pad15)") (class "Default")
      (node (ref "U2") (pin "15") (pinfunction "RS232_15") (pintype "bidirectional"))
    )
    (net (code "68") (name "unconnected-(U2-RTS-Pad14)") (class "Default")
      (node (ref "U2") (pin "14") (pinfunction "RTS_14") (pintype "bidirectional"))
    )
    (net (code "69") (name "unconnected-(U3-AREF-Pad21)") (class "Default")
      (node (ref "U3") (pin "21") (pinfunction "AREF_21") (pintype "bidirectional"))
    )
    (net (code "70") (name "unconnected-(U3-AVCC-Pad20)") (class "Default")
      (node (ref "U3") (pin "20") (pinfunction "AVCC_20") (pintype "bidirectional"))
    )
    (net (code "71") (name "unconnected-(U3-GND-Pad8)") (class "Default")
      (node (ref "U3") (pin "8") (pinfunction "GND_8") (pintype "bidirectional"))
    )
    (net (code "72") (name "unconnected-(U3-GND-Pad22)") (class "Default")
      (node (ref "U3") (pin "22") (pinfunction "GND_22") (pintype "bidirectional"))
    )
    (net (code "73") (name "unconnected-(U3-PB0(ICP)-Pad14)") (class "Default")
      (node (ref "U3") (pin "14") (pinfunction "PB0(ICP)_14") (pintype "bidirectional"))
    )
    (net (code "74") (name "unconnected-(U3-PB1(OC1A)-Pad15)") (class "Default")
      (node (ref "U3") (pin "15") (pinfunction "PB1(OC1A)_15") (pintype "bidirectional"))
    )
    (net (code "75") (name "unconnected-(U3-PB2(SS{slash}OC1B)-Pad16)") (class "Default")
      (node (ref "U3") (pin "16") (pinfunction "PB2(SS/OC1B)_16") (pintype "bidirectional"))
    )
    (net (code "76") (name "unconnected-(U3-PB3(MOSI{slash}OC2)-Pad17)") (class "Default")
      (node (ref "U3") (pin "17") (pinfunction "PB3(MOSI/OC2)_17") (pintype "bidirectional"))
    )
    (net (code "77") (name "unconnected-(U3-PB4(MISO)-Pad18)") (class "Default")
      (node (ref "U3") (pin "18") (pinfunction "PB4(MISO)_18") (pintype "bidirectional"))
    )
    (net (code "78") (name "unconnected-(U3-PB5(SCK)-Pad19)") (class "Default")
      (node (ref "U3") (pin "19") (pinfunction "PB5(SCK)_19") (pintype "bidirectional"))
    )
    (net (code "79") (name "unconnected-(U3-PB6(XTAL1{slash}TOSC1)-Pad9)") (class "Default")
      (node (ref "U3") (pin "9") (pinfunction "PB6(XTAL1/TOSC1)_9") (pintype "bidirectional"))
    )
    (net (code "80") (name "unconnected-(U3-PB7(XTAL2{slash}TOSC2)-Pad10)") (class "Default")
      (node (ref "U3") (pin "10") (pinfunction "PB7(XTAL2/TOSC2)_10") (pintype "bidirectional"))
    )
    (net (code "81") (name "unconnected-(U3-PC0(ADC0)-Pad23)") (class "Default")
      (node (ref "U3") (pin "23") (pinfunction "PC0(ADC0)_23") (pintype "bidirectional"))
    )
    (net (code "82") (name "unconnected-(U3-PC1(ADC1)-Pad24)") (class "Default")
      (node (ref "U3") (pin "24") (pinfunction "PC1(ADC1)_24") (pintype "bidirectional"))
    )
    (net (code "83") (name "unconnected-(U3-PC2(ADC2)-Pad25)") (class "Default")
      (node (ref "U3") (pin "25") (pinfunction "PC2(ADC2)_25") (pintype "bidirectional"))
    )
    (net (code "84") (name "unconnected-(U3-PC3(ADC3)-Pad26)") (class "Default")
      (node (ref "U3") (pin "26") (pinfunction "PC3(ADC3)_26") (pintype "bidirectional"))
    )
    (net (code "85") (name "unconnected-(U3-PC4(ADC4{slash}SDA)-Pad27)") (class "Default")
      (node (ref "U3") (pin "27") (pinfunction "PC4(ADC4/SDA)_27") (pintype "bidirectional"))
    )
    (net (code "86") (name "unconnected-(U3-PC5(ADC5{slash}SCL)-Pad28)") (class "Default")
      (node (ref "U3") (pin "28") (pinfunction "PC5(ADC5/SCL)_28") (pintype "bidirectional"))
    )
    (net (code "87") (name "unconnected-(U3-PC6({slash}RESET)-Pad1)") (class "Default")
      (node (ref "U3") (pin "1") (pinfunction "PC6(/RESET)_1") (pintype "bidirectional"))
    )
    (net (code "88") (name "unconnected-(U3-PD0(RXD)-Pad2)") (class "Default")
      (node (ref "U3") (pin "2") (pinfunction "PD0(RXD)_2") (pintype "bidirectional"))
    )
    (net (code "89") (name "unconnected-(U3-PD1(TXD)-Pad3)") (class "Default")
      (node (ref "U3") (pin "3") (pinfunction "PD1(TXD)_3") (pintype "bidirectional"))
    )
    (net (code "90") (name "unconnected-(U3-PD2(INT0)-Pad4)") (class "Default")
      (node (ref "U3") (pin "4") (pinfunction "PD2(INT0)_4") (pintype "bidirectional"))
    )
    (net (code "91") (name "unconnected-(U3-PD3(INT1)-Pad5)") (class "Default")
      (node (ref "U3") (pin "5") (pinfunction "PD3(INT1)_5") (pintype "bidirectional"))
    )
    (net (code "92") (name "unconnected-(U3-PD4(XCK{slash}T0)-Pad6)") (class "Default")
      (node (ref "U3") (pin "6") (pinfunction "PD4(XCK/T0)_6") (pintype "bidirectional"))
    )
    (net (code "93") (name "unconnected-(U3-PD5(T1)-Pad11)") (class "Default")
      (node (ref "U3") (pin "11") (pinfunction "PD5(T1)_11") (pintype "bidirectional"))
    )
    (net (code "94") (name "unconnected-(U3-PD6(AIN0)-Pad12)") (class "Default")
      (node (ref "U3") (pin "12") (pinfunction "PD6(AIN0)_12") (pintype "bidirectional"))
    )
    (net (code "95") (name "unconnected-(U3-PD7(AIN1)-Pad13)") (class "Default")
      (node (ref "U3") (pin "13") (pinfunction "PD7(AIN1)_13") (pintype "bidirectional"))
    )
    (net (code "96") (name "unconnected-(U3-VCC-Pad7)") (class "Default")
      (node (ref "U3") (pin "7") (pinfunction "VCC_7") (pintype "bidirectional"))
    )
    (net (code "97") (name "unconnected-(U4-AREF-Pad21)") (class "Default")
      (node (ref "U4") (pin "21") (pinfunction "AREF_21") (pintype "bidirectional"))
    )
    (net (code "98") (name "unconnected-(U4-AVCC-Pad20)") (class "Default")
      (node (ref "U4") (pin "20") (pinfunction "AVCC_20") (pintype "bidirectional"))
    )
    (net (code "99") (name "unconnected-(U4-GND-Pad8)") (class "Default")
      (node (ref "U4") (pin "8") (pinfunction "GND_8") (pintype "bidirectional"))
    )
    (net (code "100") (name "unconnected-(U4-GND-Pad22)") (class "Default")
      (node (ref "U4") (pin "22") (pinfunction "GND_22") (pintype "bidirectional"))
    )
    (net (code "101") (name "unconnected-(U4-PB0(ICP)-Pad14)") (class "Default")
      (node (ref "U4") (pin "14") (pinfunction "PB0(ICP)_14") (pintype "bidirectional"))
    )
    (net (code "102") (name "unconnected-(U4-PB1(OC1A)-Pad15)") (class "Default")
      (node (ref "U4") (pin "15") (pinfunction "PB1(OC1A)_15") (pintype "bidirectional"))
    )
    (net (code "103") (name "unconnected-(U4-PB2(SS{slash}OC1B)-Pad16)") (class "Default")
      (node (ref "U4") (pin "16") (pinfunction "PB2(SS/OC1B)_16") (pintype "bidirectional"))
    )
    (net (code "104") (name "unconnected-(U4-PB3(MOSI{slash}OC2)-Pad17)") (class "Default")
      (node (ref "U4") (pin "17") (pinfunction "PB3(MOSI/OC2)_17") (pintype "bidirectional"))
    )
    (net (code "105") (name "unconnected-(U4-PB4(MISO)-Pad18)") (class "Default")
      (node (ref "U4") (pin "18") (pinfunction "PB4(MISO)_18") (pintype "bidirectional"))
    )
    (net (code "106") (name "unconnected-(U4-PB5(SCK)-Pad19)") (class "Default")
      (node (ref "U4") (pin "19") (pinfunction "PB5(SCK)_19") (pintype "bidirectional"))
    )
    (net (code "107") (name "unconnected-(U4-PB6(XTAL1{slash}TOSC1)-Pad9)") (class "Default")
      (node (ref "U4") (pin "9") (pinfunction "PB6(XTAL1/TOSC1)_9") (pintype "bidirectional"))
    )
    (net (code "108") (name "unconnected-(U4-PB7(XTAL2{slash}TOSC2)-Pad10)") (class "Default")
      (node (ref "U4") (pin "10") (pinfunction "PB7(XTAL2/TOSC2)_10") (pintype "bidirectional"))
    )
    (net (code "109") (name "unconnected-(U4-PC0(ADC0)-Pad23)") (class "Default")
      (node (ref "U4") (pin "23") (pinfunction "PC0(ADC0)_23") (pintype "bidirectional"))
    )
    (net (code "110") (name "unconnected-(U4-PC1(ADC1)-Pad24)") (class "Default")
      (node (ref "U4") (pin "24") (pinfunction "PC1(ADC1)_24") (pintype "bidirectional"))
    )
    (net (code "111") (name "unconnected-(U4-PC2(ADC2)-Pad25)") (class "Default")
      (node (ref "U4") (pin "25") (pinfunction "PC2(ADC2)_25") (pintype "bidirectional"))
    )
    (net (code "112") (name "unconnected-(U4-PC3(ADC3)-Pad26)") (class "Default")
      (node (ref "U4") (pin "26") (pinfunction "PC3(ADC3)_26") (pintype "bidirectional"))
    )
    (net (code "113") (name "unconnected-(U4-PC4(ADC4{slash}SDA)-Pad27)") (class "Default")
      (node (ref "U4") (pin "27") (pinfunction "PC4(ADC4/SDA)_27") (pintype "bidirectional"))
    )
    (net (code "114") (name "unconnected-(U4-PC5(ADC5{slash}SCL)-Pad28)") (class "Default")
      (node (ref "U4") (pin "28") (pinfunction "PC5(ADC5/SCL)_28") (pintype "bidirectional"))
    )
    (net (code "115") (name "unconnected-(U4-PC6({slash}RESET)-Pad1)") (class "Default")
      (node (ref "U4") (pin "1") (pinfunction "PC6(/RESET)_1") (pintype "bidirectional"))
    )
    (net (code "116") (name "unconnected-(U4-PD0(RXD)-Pad2)") (class "Default")
      (node (ref "U4") (pin "2") (pinfunction "PD0(RXD)_2") (pintype "bidirectional"))
    )
    (net (code "117") (name "unconnected-(U4-PD1(TXD)-Pad3)") (class "Default")
      (node (ref "U4") (pin "3") (pinfunction "PD1(TXD)_3") (pintype "bidirectional"))
    )
    (net (code "118") (name "unconnected-(U4-PD2(INT0)-Pad4)") (class "Default")
      (node (ref "U4") (pin "4") (pinfunction "PD2(INT0)_4") (pintype "bidirectional"))
    )
    (net (code "119") (name "unconnected-(U4-PD3(INT1)-Pad5)") (class "Default")
      (node (ref "U4") (pin "5") (pinfunction "PD3(INT1)_5") (pintype "bidirectional"))
    )
    (net (code "120") (name "unconnected-(U4-PD4(XCK{slash}T0)-Pad6)") (class "Default")
      (node (ref "U4") (pin "6") (pinfunction "PD4(XCK/T0)_6") (pintype "bidirectional"))
    )
    (net (code "121") (name "unconnected-(U4-PD5(T1)-Pad11)") (class "Default")
      (node (ref "U4") (pin "11") (pinfunction "PD5(T1)_11") (pintype "bidirectional"))
    )
    (net (code "122") (name "unconnected-(U4-PD6(AIN0)-Pad12)") (class "Default")
      (node (ref "U4") (pin "12") (pinfunction "PD6(AIN0)_12") (pintype "bidirectional"))
    )
    (net (code "123") (name "unconnected-(U4-PD7(AIN1)-Pad13)") (class "Default")
      (node (ref "U4") (pin "13") (pinfunction "PD7(AIN1)_13") (pintype "bidirectional"))
    )
    (net (code "124") (name "unconnected-(U4-VCC-Pad7)") (class "Default")
      (node (ref "U4") (pin "7") (pinfunction "VCC_7") (pintype "bidirectional"))
    )
    (net (code "125") (name "unconnected-(U5-AREF-Pad21)") (class "Default")
      (node (ref "U5") (pin "21") (pinfunction "AREF_21") (pintype "bidirectional"))
    )
    (net (code "126") (name "unconnected-(U5-AVCC-Pad20)") (class "Default")
      (node (ref "U5") (pin "20") (pinfunction "AVCC_20") (pintype "bidirectional"))
    )
    (net (code "127") (name "unconnected-(U5-GND-Pad8)") (class "Default")
      (node (ref "U5") (pin "8") (pinfunction "GND_8") (pintype "bidirectional"))
    )
    (net (code "128") (name "unconnected-(U5-GND-Pad22)") (class "Default")
      (node (ref "U5") (pin "22") (pinfunction "GND_22") (pintype "bidirectional"))
    )
    (net (code "129") (name "unconnected-(U5-PB0(ICP)-Pad14)") (class "Default")
      (node (ref "U5") (pin "14") (pinfunction "PB0(ICP)_14") (pintype "bidirectional"))
    )
    (net (code "130") (name "unconnected-(U5-PB1(OC1A)-Pad15)") (class "Default")
      (node (ref "U5") (pin "15") (pinfunction "PB1(OC1A)_15") (pintype "bidirectional"))
    )
    (net (code "131") (name "unconnected-(U5-PB2(SS{slash}OC1B)-Pad16)") (class "Default")
      (node (ref "U5") (pin "16") (pinfunction "PB2(SS/OC1B)_16") (pintype "bidirectional"))
    )
    (net (code "132") (name "unconnected-(U5-PB3(MOSI{slash}OC2)-Pad17)") (class "Default")
      (node (ref "U5") (pin "17") (pinfunction "PB3(MOSI/OC2)_17") (pintype "bidirectional"))
    )
    (net (code "133") (name "unconnected-(U5-PB4(MISO)-Pad18)") (class "Default")
      (node (ref "U5") (pin "18") (pinfunction "PB4(MISO)_18") (pintype "bidirectional"))
    )
    (net (code "134") (name "unconnected-(U5-PB5(SCK)-Pad19)") (class "Default")
      (node (ref "U5") (pin "19") (pinfunction "PB5(SCK)_19") (pintype "bidirectional"))
    )
    (net (code "135") (name "unconnected-(U5-PB6(XTAL1{slash}TOSC1)-Pad9)") (class "Default")
      (node (ref "U5") (pin "9") (pinfunction "PB6(XTAL1/TOSC1)_9") (pintype "bidirectional"))
    )
    (net (code "136") (name "unconnected-(U5-PB7(XTAL2{slash}TOSC2)-Pad10)") (class "Default")
      (node (ref "U5") (pin "10") (pinfunction "PB7(XTAL2/TOSC2)_10") (pintype "bidirectional"))
    )
    (net (code "137") (name "unconnected-(U5-PC0(ADC0)-Pad23)") (class "Default")
      (node (ref "U5") (pin "23") (pinfunction "PC0(ADC0)_23") (pintype "bidirectional"))
    )
    (net (code "138") (name "unconnected-(U5-PC1(ADC1)-Pad24)") (class "Default")
      (node (ref "U5") (pin "24") (pinfunction "PC1(ADC1)_24") (pintype "bidirectional"))
    )
    (net (code "139") (name "unconnected-(U5-PC2(ADC2)-Pad25)") (class "Default")
      (node (ref "U5") (pin "25") (pinfunction "PC2(ADC2)_25") (pintype "bidirectional"))
    )
    (net (code "140") (name "unconnected-(U5-PC3(ADC3)-Pad26)") (class "Default")
      (node (ref "U5") (pin "26") (pinfunction "PC3(ADC3)_26") (pintype "bidirectional"))
    )
    (net (code "141") (name "unconnected-(U5-PC4(ADC4{slash}SDA)-Pad27)") (class "Default")
      (node (ref "U5") (pin "27") (pinfunction "PC4(ADC4/SDA)_27") (pintype "bidirectional"))
    )
    (net (code "142") (name "unconnected-(U5-PC5(ADC5{slash}SCL)-Pad28)") (class "Default")
      (node (ref "U5") (pin "28") (pinfunction "PC5(ADC5/SCL)_28") (pintype "bidirectional"))
    )
    (net (code "143") (name "unconnected-(U5-PC6({slash}RESET)-Pad1)") (class "Default")
      (node (ref "U5") (pin "1") (pinfunction "PC6(/RESET)_1") (pintype "bidirectional"))
    )
    (net (code "144") (name "unconnected-(U5-PD0(RXD)-Pad2)") (class "Default")
      (node (ref "U5") (pin "2") (pinfunction "PD0(RXD)_2") (pintype "bidirectional"))
    )
    (net (code "145") (name "unconnected-(U5-PD1(TXD)-Pad3)") (class "Default")
      (node (ref "U5") (pin "3") (pinfunction "PD1(TXD)_3") (pintype "bidirectional"))
    )
    (net (code "146") (name "unconnected-(U5-PD2(INT0)-Pad4)") (class "Default")
      (node (ref "U5") (pin "4") (pinfunction "PD2(INT0)_4") (pintype "bidirectional"))
    )
    (net (code "147") (name "unconnected-(U5-PD3(INT1)-Pad5)") (class "Default")
      (node (ref "U5") (pin "5") (pinfunction "PD3(INT1)_5") (pintype "bidirectional"))
    )
    (net (code "148") (name "unconnected-(U5-PD4(XCK{slash}T0)-Pad6)") (class "Default")
      (node (ref "U5") (pin "6") (pinfunction "PD4(XCK/T0)_6") (pintype "bidirectional"))
    )
    (net (code "149") (name "unconnected-(U5-PD5(T1)-Pad11)") (class "Default")
      (node (ref "U5") (pin "11") (pinfunction "PD5(T1)_11") (pintype "bidirectional"))
    )
    (net (code "150") (name "unconnected-(U5-PD6(AIN0)-Pad12)") (class "Default")
      (node (ref "U5") (pin "12") (pinfunction "PD6(AIN0)_12") (pintype "bidirectional"))
    )
    (net (code "151") (name "unconnected-(U5-PD7(AIN1)-Pad13)") (class "Default")
      (node (ref "U5") (pin "13") (pinfunction "PD7(AIN1)_13") (pintype "bidirectional"))
    )
    (net (code "152") (name "unconnected-(U5-VCC-Pad7)") (class "Default")
      (node (ref "U5") (pin "7") (pinfunction "VCC_7") (pintype "bidirectional"))
    )
    (net (code "153") (name "unconnected-(U7-AREF-Pad21)") (class "Default")
      (node (ref "U7") (pin "21") (pinfunction "AREF_21") (pintype "bidirectional"))
    )
    (net (code "154") (name "unconnected-(U7-AVCC-Pad20)") (class "Default")
      (node (ref "U7") (pin "20") (pinfunction "AVCC_20") (pintype "bidirectional"))
    )
    (net (code "155") (name "unconnected-(U7-GND-Pad8)") (class "Default")
      (node (ref "U7") (pin "8") (pinfunction "GND_8") (pintype "bidirectional"))
    )
    (net (code "156") (name "unconnected-(U7-GND-Pad22)") (class "Default")
      (node (ref "U7") (pin "22") (pinfunction "GND_22") (pintype "bidirectional"))
    )
    (net (code "157") (name "unconnected-(U7-PB0(ICP)-Pad14)") (class "Default")
      (node (ref "U7") (pin "14") (pinfunction "PB0(ICP)_14") (pintype "bidirectional"))
    )
    (net (code "158") (name "unconnected-(U7-PB1(OC1A)-Pad15)") (class "Default")
      (node (ref "U7") (pin "15") (pinfunction "PB1(OC1A)_15") (pintype "bidirectional"))
    )
    (net (code "159") (name "unconnected-(U7-PB2(SS{slash}OC1B)-Pad16)") (class "Default")
      (node (ref "U7") (pin "16") (pinfunction "PB2(SS/OC1B)_16") (pintype "bidirectional"))
    )
    (net (code "160") (name "unconnected-(U7-PB3(MOSI{slash}OC2)-Pad17)") (class "Default")
      (node (ref "U7") (pin "17") (pinfunction "PB3(MOSI/OC2)_17") (pintype "bidirectional"))
    )
    (net (code "161") (name "unconnected-(U7-PB4(MISO)-Pad18)") (class "Default")
      (node (ref "U7") (pin "18") (pinfunction "PB4(MISO)_18") (pintype "bidirectional"))
    )
    (net (code "162") (name "unconnected-(U7-PB5(SCK)-Pad19)") (class "Default")
      (node (ref "U7") (pin "19") (pinfunction "PB5(SCK)_19") (pintype "bidirectional"))
    )
    (net (code "163") (name "unconnected-(U7-PB6(XTAL1{slash}TOSC1)-Pad9)") (class "Default")
      (node (ref "U7") (pin "9") (pinfunction "PB6(XTAL1/TOSC1)_9") (pintype "bidirectional"))
    )
    (net (code "164") (name "unconnected-(U7-PB7(XTAL2{slash}TOSC2)-Pad10)") (class "Default")
      (node (ref "U7") (pin "10") (pinfunction "PB7(XTAL2/TOSC2)_10") (pintype "bidirectional"))
    )
    (net (code "165") (name "unconnected-(U7-PC0(ADC0)-Pad23)") (class "Default")
      (node (ref "U7") (pin "23") (pinfunction "PC0(ADC0)_23") (pintype "bidirectional"))
    )
    (net (code "166") (name "unconnected-(U7-PC1(ADC1)-Pad24)") (class "Default")
      (node (ref "U7") (pin "24") (pinfunction "PC1(ADC1)_24") (pintype "bidirectional"))
    )
    (net (code "167") (name "unconnected-(U7-PC2(ADC2)-Pad25)") (class "Default")
      (node (ref "U7") (pin "25") (pinfunction "PC2(ADC2)_25") (pintype "bidirectional"))
    )
    (net (code "168") (name "unconnected-(U7-PC3(ADC3)-Pad26)") (class "Default")
      (node (ref "U7") (pin "26") (pinfunction "PC3(ADC3)_26") (pintype "bidirectional"))
    )
    (net (code "169") (name "unconnected-(U7-PC4(ADC4{slash}SDA)-Pad27)") (class "Default")
      (node (ref "U7") (pin "27") (pinfunction "PC4(ADC4/SDA)_27") (pintype "bidirectional"))
    )
    (net (code "170") (name "unconnected-(U7-PC5(ADC5{slash}SCL)-Pad28)") (class "Default")
      (node (ref "U7") (pin "28") (pinfunction "PC5(ADC5/SCL)_28") (pintype "bidirectional"))
    )
    (net (code "171") (name "unconnected-(U7-PC6({slash}RESET)-Pad1)") (class "Default")
      (node (ref "U7") (pin "1") (pinfunction "PC6(/RESET)_1") (pintype "bidirectional"))
    )
    (net (code "172") (name "unconnected-(U7-PD0(RXD)-Pad2)") (class "Default")
      (node (ref "U7") (pin "2") (pinfunction "PD0(RXD)_2") (pintype "bidirectional"))
    )
    (net (code "173") (name "unconnected-(U7-PD1(TXD)-Pad3)") (class "Default")
      (node (ref "U7") (pin "3") (pinfunction "PD1(TXD)_3") (pintype "bidirectional"))
    )
    (net (code "174") (name "unconnected-(U7-PD2(INT0)-Pad4)") (class "Default")
      (node (ref "U7") (pin "4") (pinfunction "PD2(INT0)_4") (pintype "bidirectional"))
    )
    (net (code "175") (name "unconnected-(U7-PD3(INT1)-Pad5)") (class "Default")
      (node (ref "U7") (pin "5") (pinfunction "PD3(INT1)_5") (pintype "bidirectional"))
    )
    (net (code "176") (name "unconnected-(U7-PD4(XCK{slash}T0)-Pad6)") (class "Default")
      (node (ref "U7") (pin "6") (pinfunction "PD4(XCK/T0)_6") (pintype "bidirectional"))
    )
    (net (code "177") (name "unconnected-(U7-PD5(T1)-Pad11)") (class "Default")
      (node (ref "U7") (pin "11") (pinfunction "PD5(T1)_11") (pintype "bidirectional"))
    )
    (net (code "178") (name "unconnected-(U7-PD6(AIN0)-Pad12)") (class "Default")
      (node (ref "U7") (pin "12") (pinfunction "PD6(AIN0)_12") (pintype "bidirectional"))
    )
    (net (code "179") (name "unconnected-(U7-PD7(AIN1)-Pad13)") (class "Default")
      (node (ref "U7") (pin "13") (pinfunction "PD7(AIN1)_13") (pintype "bidirectional"))
    )
    (net (code "180") (name "unconnected-(U7-VCC-Pad7)") (class "Default")
      (node (ref "U7") (pin "7") (pinfunction "VCC_7") (pintype "bidirectional"))
    )
    (net (code "181") (name "unconnected-(ZX1-Pad2)") (class "Default")
      (node (ref "ZX1") (pin "2") (pinfunction "2_2") (pintype "passive"))
    )
    (net (code "182") (name "unconnected-(ZX1-Pad3)") (class "Default")
      (node (ref "ZX1") (pin "3") (pinfunction "3_3") (pintype "passive"))
    )
    (net (code "183") (name "unconnected-(ZX1-Pad4)") (class "Default")
      (node (ref "ZX1") (pin "4") (pinfunction "4_4") (pintype "passive"))
    )
    (net (code "184") (name "unconnected-(ZX1-Pad5)") (class "Default")
      (node (ref "ZX1") (pin "5") (pinfunction "5_5") (pintype "passive"))
    )
    (net (code "185") (name "unconnected-(ZX1-Pad6)") (class "Default")
      (node (ref "ZX1") (pin "6") (pinfunction "6_6") (pintype "passive"))
    )
    (net (code "186") (name "unconnected-(ZX1-Pad10)") (class "Default")
      (node (ref "ZX1") (pin "10") (pinfunction "10_10") (pintype "passive"))
    )
    (net (code "187") (name "unconnected-(ZX1-Pad11)") (class "Default")
      (node (ref "ZX1") (pin "11") (pinfunction "11_11") (pintype "passive"))
    )
    (net (code "188") (name "unconnected-(ZX1-Pad12)") (class "Default")
      (node (ref "ZX1") (pin "12") (pinfunction "12_12") (pintype "passive"))
    )
    (net (code "189") (name "unconnected-(ZX1-Pad13)") (class "Default")
      (node (ref "ZX1") (pin "13") (pinfunction "13_13") (pintype "passive"))
    )
    (net (code "190") (name "unconnected-(ZX1-Pad14)") (class "Default")
      (node (ref "ZX1") (pin "14") (pinfunction "14_14") (pintype "passive"))
    )
    (net (code "191") (name "unconnected-(ZX1-Pad15)") (class "Default")
      (node (ref "ZX1") (pin "15") (pinfunction "15_15") (pintype "passive"))
    )
    (net (code "192") (name "unconnected-(ZX1-Pad16)") (class "Default")
      (node (ref "ZX1") (pin "16") (pinfunction "16_16") (pintype "passive"))
    )
    (net (code "193") (name "unconnected-(ZX1-Pad20)") (class "Default")
      (node (ref "ZX1") (pin "20") (pinfunction "20_20") (pintype "passive"))
    )
    (net (code "194") (name "unconnected-(ZX1-Pad21)") (class "Default")
      (node (ref "ZX1") (pin "21") (pinfunction "21_21") (pintype "passive"))
    )
    (net (code "195") (name "unconnected-(ZX1-Pad23)") (class "Default")
      (node (ref "ZX1") (pin "23") (pinfunction "23_23") (pintype "passive"))
    )
    (net (code "196") (name "unconnected-(ZX1-Pad24)") (class "Default")
      (node (ref "ZX1") (pin "24") (pinfunction "24_24") (pintype "passive"))
    )
    (net (code "197") (name "unconnected-(ZX1-Pad25)") (class "Default")
      (node (ref "ZX1") (pin "25") (pinfunction "25_25") (pintype "passive"))
    )
    (net (code "198") (name "unconnected-(ZX1-Pad26)") (class "Default")
      (node (ref "ZX1") (pin "26") (pinfunction "26_26") (pintype "passive"))
    )
    (net (code "199") (name "unconnected-(ZX1-Pad27)") (class "Default")
      (node (ref "ZX1") (pin "27") (pinfunction "27_27") (pintype "passive"))
    )
    (net (code "200") (name "unconnected-(ZX1-Pad28)") (class "Default")
      (node (ref "ZX1") (pin "28") (pinfunction "28_28") (pintype "passive"))
    )
    (net (code "201") (name "unconnected-(ZX2-Pad2)") (class "Default")
      (node (ref "ZX2") (pin "2") (pinfunction "2_2") (pintype "passive"))
    )
    (net (code "202") (name "unconnected-(ZX2-Pad3)") (class "Default")
      (node (ref "ZX2") (pin "3") (pinfunction "3_3") (pintype "passive"))
    )
    (net (code "203") (name "unconnected-(ZX2-Pad4)") (class "Default")
      (node (ref "ZX2") (pin "4") (pinfunction "4_4") (pintype "passive"))
    )
    (net (code "204") (name "unconnected-(ZX2-Pad5)") (class "Default")
      (node (ref "ZX2") (pin "5") (pinfunction "5_5") (pintype "passive"))
    )
    (net (code "205") (name "unconnected-(ZX2-Pad6)") (class "Default")
      (node (ref "ZX2") (pin "6") (pinfunction "6_6") (pintype "passive"))
    )
    (net (code "206") (name "unconnected-(ZX2-Pad10)") (class "Default")
      (node (ref "ZX2") (pin "10") (pinfunction "10_10") (pintype "passive"))
    )
    (net (code "207") (name "unconnected-(ZX2-Pad11)") (class "Default")
      (node (ref "ZX2") (pin "11") (pinfunction "11_11") (pintype "passive"))
    )
    (net (code "208") (name "unconnected-(ZX2-Pad12)") (class "Default")
      (node (ref "ZX2") (pin "12") (pinfunction "12_12") (pintype "passive"))
    )
    (net (code "209") (name "unconnected-(ZX2-Pad13)") (class "Default")
      (node (ref "ZX2") (pin "13") (pinfunction "13_13") (pintype "passive"))
    )
    (net (code "210") (name "unconnected-(ZX2-Pad14)") (class "Default")
      (node (ref "ZX2") (pin "14") (pinfunction "14_14") (pintype "passive"))
    )
    (net (code "211") (name "unconnected-(ZX2-Pad15)") (class "Default")
      (node (ref "ZX2") (pin "15") (pinfunction "15_15") (pintype "passive"))
    )
    (net (code "212") (name "unconnected-(ZX2-Pad16)") (class "Default")
      (node (ref "ZX2") (pin "16") (pinfunction "16_16") (pintype "passive"))
    )
    (net (code "213") (name "unconnected-(ZX2-Pad20)") (class "Default")
      (node (ref "ZX2") (pin "20") (pinfunction "20_20") (pintype "passive"))
    )
    (net (code "214") (name "unconnected-(ZX2-Pad21)") (class "Default")
      (node (ref "ZX2") (pin "21") (pinfunction "21_21") (pintype "passive"))
    )
    (net (code "215") (name "unconnected-(ZX2-Pad23)") (class "Default")
      (node (ref "ZX2") (pin "23") (pinfunction "23_23") (pintype "passive"))
    )
    (net (code "216") (name "unconnected-(ZX2-Pad24)") (class "Default")
      (node (ref "ZX2") (pin "24") (pinfunction "24_24") (pintype "passive"))
    )
    (net (code "217") (name "unconnected-(ZX2-Pad25)") (class "Default")
      (node (ref "ZX2") (pin "25") (pinfunction "25_25") (pintype "passive"))
    )
    (net (code "218") (name "unconnected-(ZX2-Pad26)") (class "Default")
      (node (ref "ZX2") (pin "26") (pinfunction "26_26") (pintype "passive"))
    )
    (net (code "219") (name "unconnected-(ZX2-Pad27)") (class "Default")
      (node (ref "ZX2") (pin "27") (pinfunction "27_27") (pintype "passive"))
    )
    (net (code "220") (name "unconnected-(ZX2-Pad28)") (class "Default")
      (node (ref "ZX2") (pin "28") (pinfunction "28_28") (pintype "passive"))
    )
    (net (code "221") (name "unconnected-(ZX3-Pad2)") (class "Default")
      (node (ref "ZX3") (pin "2") (pinfunction "2_2") (pintype "passive"))
    )
    (net (code "222") (name "unconnected-(ZX3-Pad3)") (class "Default")
      (node (ref "ZX3") (pin "3") (pinfunction "3_3") (pintype "passive"))
    )
    (net (code "223") (name "unconnected-(ZX3-Pad4)") (class "Default")
      (node (ref "ZX3") (pin "4") (pinfunction "4_4") (pintype "passive"))
    )
    (net (code "224") (name "unconnected-(ZX3-Pad5)") (class "Default")
      (node (ref "ZX3") (pin "5") (pinfunction "5_5") (pintype "passive"))
    )
    (net (code "225") (name "unconnected-(ZX3-Pad6)") (class "Default")
      (node (ref "ZX3") (pin "6") (pinfunction "6_6") (pintype "passive"))
    )
    (net (code "226") (name "unconnected-(ZX3-Pad10)") (class "Default")
      (node (ref "ZX3") (pin "10") (pinfunction "10_10") (pintype "passive"))
    )
    (net (code "227") (name "unconnected-(ZX3-Pad11)") (class "Default")
      (node (ref "ZX3") (pin "11") (pinfunction "11_11") (pintype "passive"))
    )
    (net (code "228") (name "unconnected-(ZX3-Pad12)") (class "Default")
      (node (ref "ZX3") (pin "12") (pinfunction "12_12") (pintype "passive"))
    )
    (net (code "229") (name "unconnected-(ZX3-Pad13)") (class "Default")
      (node (ref "ZX3") (pin "13") (pinfunction "13_13") (pintype "passive"))
    )
    (net (code "230") (name "unconnected-(ZX3-Pad14)") (class "Default")
      (node (ref "ZX3") (pin "14") (pinfunction "14_14") (pintype "passive"))
    )
    (net (code "231") (name "unconnected-(ZX3-Pad15)") (class "Default")
      (node (ref "ZX3") (pin "15") (pinfunction "15_15") (pintype "passive"))
    )
    (net (code "232") (name "unconnected-(ZX3-Pad16)") (class "Default")
      (node (ref "ZX3") (pin "16") (pinfunction "16_16") (pintype "passive"))
    )
    (net (code "233") (name "unconnected-(ZX3-Pad20)") (class "Default")
      (node (ref "ZX3") (pin "20") (pinfunction "20_20") (pintype "passive"))
    )
    (net (code "234") (name "unconnected-(ZX3-Pad21)") (class "Default")
      (node (ref "ZX3") (pin "21") (pinfunction "21_21") (pintype "passive"))
    )
    (net (code "235") (name "unconnected-(ZX3-Pad23)") (class "Default")
      (node (ref "ZX3") (pin "23") (pinfunction "23_23") (pintype "passive"))
    )
    (net (code "236") (name "unconnected-(ZX3-Pad24)") (class "Default")
      (node (ref "ZX3") (pin "24") (pinfunction "24_24") (pintype "passive"))
    )
    (net (code "237") (name "unconnected-(ZX3-Pad25)") (class "Default")
      (node (ref "ZX3") (pin "25") (pinfunction "25_25") (pintype "passive"))
    )
    (net (code "238") (name "unconnected-(ZX3-Pad26)") (class "Default")
      (node (ref "ZX3") (pin "26") (pinfunction "26_26") (pintype "passive"))
    )
    (net (code "239") (name "unconnected-(ZX3-Pad27)") (class "Default")
      (node (ref "ZX3") (pin "27") (pinfunction "27_27") (pintype "passive"))
    )
    (net (code "240") (name "unconnected-(ZX3-Pad28)") (class "Default")
      (node (ref "ZX3") (pin "28") (pinfunction "28_28") (pintype "passive"))
    )
    (net (code "241") (name "unconnected-(ZX4-Pad2)") (class "Default")
      (node (ref "ZX4") (pin "2") (pinfunction "2_2") (pintype "passive"))
    )
    (net (code "242") (name "unconnected-(ZX4-Pad3)") (class "Default")
      (node (ref "ZX4") (pin "3") (pinfunction "3_3") (pintype "passive"))
    )
    (net (code "243") (name "unconnected-(ZX4-Pad4)") (class "Default")
      (node (ref "ZX4") (pin "4") (pinfunction "4_4") (pintype "passive"))
    )
    (net (code "244") (name "unconnected-(ZX4-Pad5)") (class "Default")
      (node (ref "ZX4") (pin "5") (pinfunction "5_5") (pintype "passive"))
    )
    (net (code "245") (name "unconnected-(ZX4-Pad6)") (class "Default")
      (node (ref "ZX4") (pin "6") (pinfunction "6_6") (pintype "passive"))
    )
    (net (code "246") (name "unconnected-(ZX4-Pad10)") (class "Default")
      (node (ref "ZX4") (pin "10") (pinfunction "10_10") (pintype "passive"))
    )
    (net (code "247") (name "unconnected-(ZX4-Pad11)") (class "Default")
      (node (ref "ZX4") (pin "11") (pinfunction "11_11") (pintype "passive"))
    )
    (net (code "248") (name "unconnected-(ZX4-Pad12)") (class "Default")
      (node (ref "ZX4") (pin "12") (pinfunction "12_12") (pintype "passive"))
    )
    (net (code "249") (name "unconnected-(ZX4-Pad13)") (class "Default")
      (node (ref "ZX4") (pin "13") (pinfunction "13_13") (pintype "passive"))
    )
    (net (code "250") (name "unconnected-(ZX4-Pad14)") (class "Default")
      (node (ref "ZX4") (pin "14") (pinfunction "14_14") (pintype "passive"))
    )
    (net (code "251") (name "unconnected-(ZX4-Pad15)") (class "Default")
      (node (ref "ZX4") (pin "15") (pinfunction "15_15") (pintype "passive"))
    )
    (net (code "252") (name "unconnected-(ZX4-Pad16)") (class "Default")
      (node (ref "ZX4") (pin "16") (pinfunction "16_16") (pintype "passive"))
    )
    (net (code "253") (name "unconnected-(ZX4-Pad20)") (class "Default")
      (node (ref "ZX4") (pin "20") (pinfunction "20_20") (pintype "passive"))
    )
    (net (code "254") (name "unconnected-(ZX4-Pad21)") (class "Default")
      (node (ref "ZX4") (pin "21") (pinfunction "21_21") (pintype "passive"))
    )
    (net (code "255") (name "unconnected-(ZX4-Pad23)") (class "Default")
      (node (ref "ZX4") (pin "23") (pinfunction "23_23") (pintype "passive"))
    )
    (net (code "256") (name "unconnected-(ZX4-Pad24)") (class "Default")
      (node (ref "ZX4") (pin "24") (pinfunction "24_24") (pintype "passive"))
    )
    (net (code "257") (name "unconnected-(ZX4-Pad25)") (class "Default")
      (node (ref "ZX4") (pin "25") (pinfunction "25_25") (pintype "passive"))
    )
    (net (code "258") (name "unconnected-(ZX4-Pad26)") (class "Default")
      (node (ref "ZX4") (pin "26") (pinfunction "26_26") (pintype "passive"))
    )
    (net (code "259") (name "unconnected-(ZX4-Pad27)") (class "Default")
      (node (ref "ZX4") (pin "27") (pinfunction "27_27") (pintype "passive"))
    )
    (net (code "260") (name "unconnected-(ZX4-Pad28)") (class "Default")
      (node (ref "ZX4") (pin "28") (pinfunction "28_28") (pintype "passive"))
    )
  )
)
